# STM32MP25XXAK_I_Os.net
KiCad netlist of a schematic drawn in Altium Designer
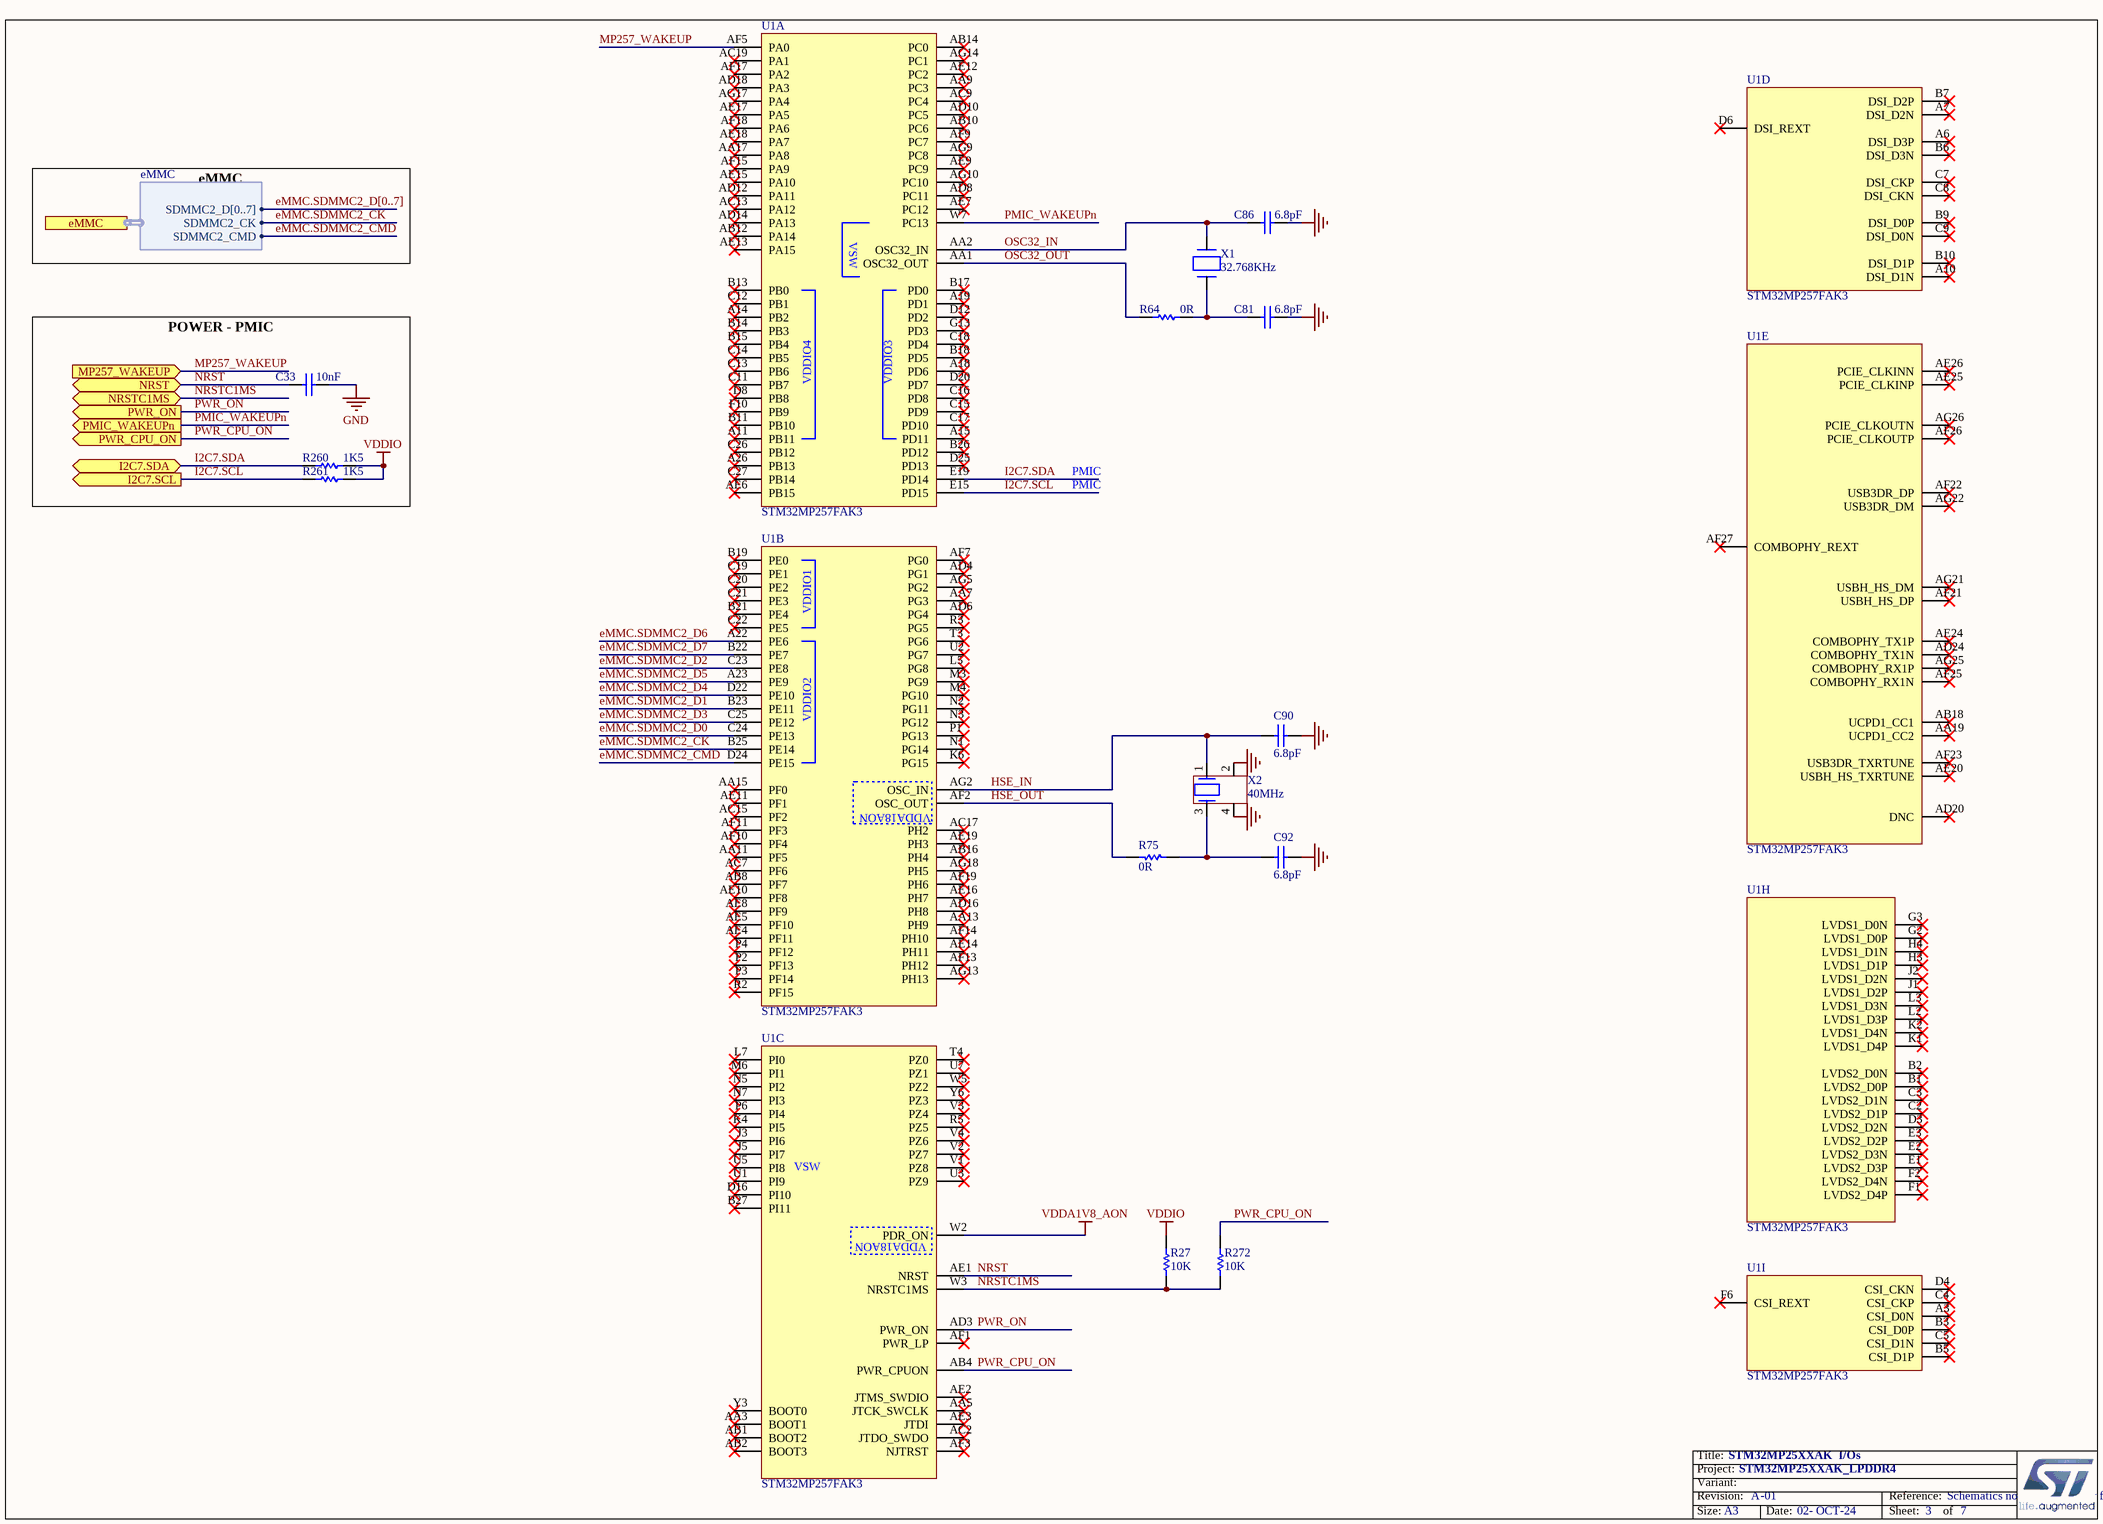
[diagram p0: STM32MP25XXAK I_Os.SchDoc]

(export (version "E")
  (design (tool "Eeschema 10.0.6"))
  (components
    (comp (ref "C33")
      (value "10nF")
      (footprint "C0402")
      (description "Capacitor, MLCC, 10nF, 16V, X7R, 10%, 0402, T=0.5mm")
      (fields
        (field (name "INTERNAL_PART_NUMBER") "MCD-00011")
        (field (name "MANUFACTURER_PART_NUMBER") "CC0402KRX7R7BB103")
        (field (name "PROVIDED_BY") "SUBCO")
      )
      (libsource (lib "MCD_PARTS_database") (part "Capacitor"))
    )
    (comp (ref "C81")
      (value "6.8pF")
      (footprint "C0402")
      (description "Capacitor, MLCC, 6.8pF, 50V, NPO, +-0.25pF, 0402, T=0.5mm")
      (fields
        (field (name "INTERNAL_PART_NUMBER") "MCD-00674")
        (field (name "MANUFACTURER_PART_NUMBER") "CC0402CRNPO9BN6R8")
        (field (name "PROVIDED_BY") "SUBCO")
      )
      (libsource (lib "MCD_PARTS_database") (part "Capacitor"))
    )
    (comp (ref "C86")
      (value "6.8pF")
      (footprint "C0402")
      (description "Capacitor, MLCC, 6.8pF, 50V, NPO, +-0.25pF, 0402, T=0.5mm")
      (fields
        (field (name "INTERNAL_PART_NUMBER") "MCD-00674")
        (field (name "MANUFACTURER_PART_NUMBER") "CC0402CRNPO9BN6R8")
        (field (name "PROVIDED_BY") "SUBCO")
      )
      (libsource (lib "MCD_PARTS_database") (part "Capacitor"))
    )
    (comp (ref "C90")
      (value "6.8pF")
      (footprint "C0402")
      (description "Capacitor, MLCC, 6.8pF, 50V, NPO, +-0.25pF, 0402, T=0.5mm")
      (fields
        (field (name "INTERNAL_PART_NUMBER") "MCD-00674")
        (field (name "MANUFACTURER_PART_NUMBER") "CC0402CRNPO9BN6R8")
        (field (name "PROVIDED_BY") "SUBCO")
      )
      (libsource (lib "MCD_PARTS_database") (part "Capacitor"))
    )
    (comp (ref "C92")
      (value "6.8pF")
      (footprint "C0402")
      (description "Capacitor, MLCC, 6.8pF, 50V, NPO, +-0.25pF, 0402, T=0.5mm")
      (fields
        (field (name "INTERNAL_PART_NUMBER") "MCD-00674")
        (field (name "MANUFACTURER_PART_NUMBER") "CC0402CRNPO9BN6R8")
        (field (name "PROVIDED_BY") "SUBCO")
      )
      (libsource (lib "MCD_PARTS_database") (part "Capacitor"))
    )
    (comp (ref "R27")
      (value "10K")
      (footprint "R0402")
      (description "Resistor,10K,0402,1%,1/16W")
      (fields (field (name "INTERNAL_PART_NUMBER") "MCD-00053") (field (name "BMS_PART_NUMBER") "9131590"))
      (libsource (lib "MCD_PARTS_database") (part "Resistor"))
    )
    (comp (ref "R64")
      (value "0R")
      (footprint "R0402")
      (description "Resistor,0R,0402,5%,1/16W")
      (fields
        (field (name "INTERNAL_PART_NUMBER") "MCD-00052")
        (field (name "MANUFACTURER_PART_NUMBER") "RC0402JR-070RL")
        (field (name "PROVIDED_BY") "SUBCO")
      )
      (libsource (lib "MCD_PARTS_database") (part "Resistor"))
    )
    (comp (ref "R75")
      (value "0R")
      (footprint "R0402")
      (description "Resistor,0R,0402,5%,1/16W")
      (fields
        (field (name "INTERNAL_PART_NUMBER") "MCD-00052")
        (field (name "MANUFACTURER_PART_NUMBER") "RC0402JR-070RL")
        (field (name "PROVIDED_BY") "SUBCO")
      )
      (libsource (lib "MCD_PARTS_database") (part "Resistor"))
    )
    (comp (ref "R260")
      (value "1K5")
      (footprint "R0402")
      (description "Resistor,1K5,0402,1%,1/16W")
      (fields (field (name "INTERNAL_PART_NUMBER") "MCD-00068") (field (name "MANUFACTURER") "YAGEO"))
      (libsource (lib "MCD_PARTS_database") (part "Resistor"))
    )
    (comp (ref "R261")
      (value "1K5")
      (footprint "R0402")
      (description "Resistor,1K5,0402,1%,1/16W")
      (fields (field (name "INTERNAL_PART_NUMBER") "MCD-00068") (field (name "MANUFACTURER") "YAGEO"))
      (libsource (lib "MCD_PARTS_database") (part "Resistor"))
    )
    (comp (ref "R272")
      (value "10K")
      (footprint "R0402")
      (description "Resistor,10K,0402,1%,1/16W")
      (fields (field (name "INTERNAL_PART_NUMBER") "MCD-00053") (field (name "BMS_PART_NUMBER") "9131590"))
      (libsource (lib "MCD_PARTS_database") (part "Resistor"))
    )
    (comp (ref "U1")
      (value "STM32MP257FAK3")
      (footprint "ICC_TFBGA424_14X14_P050_H1P20_CODE-B0A2")
      (description "MPU , 2xCortex-A35@1.5GHz, Cortex-M33@400MHz, TFBGA 14x14, pitch 0.5, 808 KB SRAM, With Crypto")
      (fields
        (field (name "INTERNAL_PART_NUMBER") "MCD-03375")
        (field (name "MANUFACTURER") "STMICROELECTRONICS")
      )
      (libsource (lib "MCD_PARTS_database") (part "STM32MP257FAK3"))
    )
    (comp (ref "X1")
      (value "32.768KHz")
      (footprint "CRY_NX2012SA_2P")
      (description "Crystal, 32.768kHz, 6pF, +/-20ppm, 80K, 2.05x1.2mm")
      (fields (field (name "INTERNAL_PART_NUMBER") "MCD-01479") (field (name "BMS_PART_NUMBER") "9157049"))
      (libsource (lib "MCD_PARTS_database") (part "XTAL_2_PINS"))
    )
    (comp (ref "X2")
      (value "40MHz")
      (footprint "CRY_NX1612SA_4P")
      (description "Crystal, 40MHz, 6pF, +/-20ppm, 80R, 1.6x1.2mm")
      (fields (field (name "INTERNAL_PART_NUMBER") "MCD-02344") (field (name "MANUFACTURER") "NDK"))
      (libsource (lib "MCD_PARTS_database") (part "XTAL_4_PINS"))
    )
  )
  (nets
    (net (code "2") (name "/HSE_IN") (class "Default")
      (node (ref "C90") (pin "2") (pinfunction "2_2") (pintype "passive"))
      (node (ref "U1") (pin "AG2") (pinfunction "OSC_IN_AG2") (pintype "passive"))
      (node (ref "X2") (pin "1") (pinfunction "1_1") (pintype "passive"))
    )
    (net (code "3") (name "/HSE_OUT") (class "Default")
      (node (ref "R75") (pin "2") (pinfunction "2_2") (pintype "passive"))
      (node (ref "U1") (pin "AF2") (pinfunction "OSC_OUT_AF2") (pintype "passive"))
    )
    (net (code "4") (name "/I2C7.SCL") (class "Default")
      (node (ref "R261") (pin "1") (pinfunction "1_1") (pintype "passive"))
      (node (ref "U1") (pin "E15") (pinfunction "PD15_E15") (pintype "passive"))
    )
    (net (code "5") (name "/I2C7.SDA") (class "Default")
      (node (ref "R260") (pin "1") (pinfunction "1_1") (pintype "passive"))
      (node (ref "U1") (pin "E19") (pinfunction "PD14_E19") (pintype "passive"))
    )
    (net (code "6") (name "/MP257_WAKEUP") (class "Default")
      (node (ref "U1") (pin "AF5") (pinfunction "PA0_AF5") (pintype "passive"))
    )
    (net (code "7") (name "/NRST") (class "Default")
      (node (ref "C33") (pin "2") (pinfunction "2_2") (pintype "passive"))
      (node (ref "U1") (pin "AE1") (pinfunction "NRST_AE1") (pintype "passive"))
    )
    (net (code "8") (name "/NRSTC1MS") (class "Default")
      (node (ref "R27") (pin "1") (pinfunction "1_1") (pintype "passive"))
      (node (ref "R272") (pin "1") (pinfunction "1_1") (pintype "passive"))
      (node (ref "U1") (pin "W3") (pinfunction "NRSTC1MS_W3") (pintype "passive"))
    )
    (net (code "9") (name "/OSC32_IN") (class "Default")
      (node (ref "C86") (pin "1") (pinfunction "1_1") (pintype "passive"))
      (node (ref "U1") (pin "AA2") (pinfunction "OSC32_IN_AA2") (pintype "passive"))
      (node (ref "X1") (pin "2") (pinfunction "X2_2") (pintype "passive"))
    )
    (net (code "10") (name "/OSC32_OUT") (class "Default")
      (node (ref "R64") (pin "1") (pinfunction "1_1") (pintype "passive"))
      (node (ref "U1") (pin "AA1") (pinfunction "OSC32_OUT_AA1") (pintype "passive"))
    )
    (net (code "11") (name "/PMIC_WAKEUPn") (class "Default")
      (node (ref "U1") (pin "W7") (pinfunction "PC13_W7") (pintype "passive"))
    )
    (net (code "12") (name "/PWR_CPU_ON") (class "Default")
      (node (ref "R272") (pin "2") (pinfunction "2_2") (pintype "passive"))
      (node (ref "U1") (pin "AB4") (pinfunction "PWR_CPUON_AB4") (pintype "passive"))
    )
    (net (code "13") (name "/PWR_ON") (class "Default")
      (node (ref "U1") (pin "AD3") (pinfunction "PWR_ON_AD3") (pintype "passive"))
    )
    (net (code "14") (name "/eMMC.SDMMC2_CK") (class "Default")
      (node (ref "U1") (pin "B25") (pinfunction "PE14_B25") (pintype "passive"))
    )
    (net (code "15") (name "/eMMC.SDMMC2_CMD") (class "Default")
      (node (ref "U1") (pin "D24") (pinfunction "PE15_D24") (pintype "passive"))
    )
    (net (code "16") (name "/eMMC.SDMMC2_D0") (class "Default")
      (node (ref "U1") (pin "C24") (pinfunction "PE13_C24") (pintype "passive"))
    )
    (net (code "17") (name "/eMMC.SDMMC2_D1") (class "Default")
      (node (ref "U1") (pin "B23") (pinfunction "PE11_B23") (pintype "passive"))
    )
    (net (code "18") (name "/eMMC.SDMMC2_D2") (class "Default")
      (node (ref "U1") (pin "C23") (pinfunction "PE8_C23") (pintype "passive"))
    )
    (net (code "19") (name "/eMMC.SDMMC2_D3") (class "Default")
      (node (ref "U1") (pin "C25") (pinfunction "PE12_C25") (pintype "passive"))
    )
    (net (code "20") (name "/eMMC.SDMMC2_D4") (class "Default")
      (node (ref "U1") (pin "D22") (pinfunction "PE10_D22") (pintype "passive"))
    )
    (net (code "21") (name "/eMMC.SDMMC2_D5") (class "Default")
      (node (ref "U1") (pin "A23") (pinfunction "PE9_A23") (pintype "passive"))
    )
    (net (code "22") (name "/eMMC.SDMMC2_D6") (class "Default")
      (node (ref "U1") (pin "A22") (pinfunction "PE6_A22") (pintype "passive"))
    )
    (net (code "23") (name "/eMMC.SDMMC2_D7") (class "Default")
      (node (ref "U1") (pin "B22") (pinfunction "PE7_B22") (pintype "passive"))
    )
    (net (code "26") (name "GND") (class "Default")
      (node (ref "C33") (pin "1") (pinfunction "1_1") (pintype "passive"))
      (node (ref "C81") (pin "2") (pinfunction "2_2") (pintype "passive"))
      (node (ref "C86") (pin "2") (pinfunction "2_2") (pintype "passive"))
      (node (ref "C90") (pin "1") (pinfunction "1_1") (pintype "passive"))
      (node (ref "C92") (pin "2") (pinfunction "2_2") (pintype "passive"))
      (node (ref "X2") (pin "2") (pinfunction "2_2") (pintype "passive"))
      (node (ref "X2") (pin "4") (pinfunction "4_4") (pintype "passive"))
    )
    (net (code "27") (name "Net-(C92-Pad1)") (class "Default")
      (node (ref "C92") (pin "1") (pinfunction "1_1") (pintype "passive"))
      (node (ref "R75") (pin "1") (pinfunction "1_1") (pintype "passive"))
      (node (ref "X2") (pin "3") (pinfunction "3_3") (pintype "passive"))
    )
    (net (code "28") (name "Net-(X1-X1)") (class "Default")
      (node (ref "C81") (pin "1") (pinfunction "1_1") (pintype "passive"))
      (node (ref "R64") (pin "2") (pinfunction "2_2") (pintype "passive"))
      (node (ref "X1") (pin "1") (pinfunction "X1_1") (pintype "passive"))
    )
    (net (code "29") (name "VDDA1V8_AON") (class "Default")
      (node (ref "U1") (pin "W2") (pinfunction "PDR_ON_W2") (pintype "passive"))
    )
    (net (code "30") (name "VDDIO") (class "Default")
      (node (ref "R260") (pin "2") (pinfunction "2_2") (pintype "passive"))
      (node (ref "R261") (pin "2") (pinfunction "2_2") (pintype "passive"))
      (node (ref "R27") (pin "2") (pinfunction "2_2") (pintype "passive"))
    )
    (net (code "31") (name "unconnected-(U1A-PA1-PadAC19)") (class "Default")
      (node (ref "U1") (pin "AC19") (pinfunction "PA1_AC19") (pintype "passive+no_connect"))
    )
    (net (code "32") (name "unconnected-(U1A-PA2-PadAF17)") (class "Default")
      (node (ref "U1") (pin "AF17") (pinfunction "PA2_AF17") (pintype "passive+no_connect"))
    )
    (net (code "33") (name "unconnected-(U1A-PA3-PadAD18)") (class "Default")
      (node (ref "U1") (pin "AD18") (pinfunction "PA3_AD18") (pintype "passive+no_connect"))
    )
    (net (code "34") (name "unconnected-(U1A-PA4-PadAG17)") (class "Default")
      (node (ref "U1") (pin "AG17") (pinfunction "PA4_AG17") (pintype "passive+no_connect"))
    )
    (net (code "35") (name "unconnected-(U1A-PA5-PadAE17)") (class "Default")
      (node (ref "U1") (pin "AE17") (pinfunction "PA5_AE17") (pintype "passive+no_connect"))
    )
    (net (code "36") (name "unconnected-(U1A-PA6-PadAF18)") (class "Default")
      (node (ref "U1") (pin "AF18") (pinfunction "PA6_AF18") (pintype "passive+no_connect"))
    )
    (net (code "37") (name "unconnected-(U1A-PA7-PadAE18)") (class "Default")
      (node (ref "U1") (pin "AE18") (pinfunction "PA7_AE18") (pintype "passive+no_connect"))
    )
    (net (code "38") (name "unconnected-(U1A-PA8-PadAA17)") (class "Default")
      (node (ref "U1") (pin "AA17") (pinfunction "PA8_AA17") (pintype "passive+no_connect"))
    )
    (net (code "39") (name "unconnected-(U1A-PA9-PadAF15)") (class "Default")
      (node (ref "U1") (pin "AF15") (pinfunction "PA9_AF15") (pintype "passive+no_connect"))
    )
    (net (code "40") (name "unconnected-(U1A-PA10-PadAE15)") (class "Default")
      (node (ref "U1") (pin "AE15") (pinfunction "PA10_AE15") (pintype "passive+no_connect"))
    )
    (net (code "41") (name "unconnected-(U1A-PA11-PadAD12)") (class "Default")
      (node (ref "U1") (pin "AD12") (pinfunction "PA11_AD12") (pintype "passive+no_connect"))
    )
    (net (code "42") (name "unconnected-(U1A-PA12-PadAC13)") (class "Default")
      (node (ref "U1") (pin "AC13") (pinfunction "PA12_AC13") (pintype "passive+no_connect"))
    )
    (net (code "43") (name "unconnected-(U1A-PA13-PadAD14)") (class "Default")
      (node (ref "U1") (pin "AD14") (pinfunction "PA13_AD14") (pintype "passive+no_connect"))
    )
    (net (code "44") (name "unconnected-(U1A-PA14-PadAB12)") (class "Default")
      (node (ref "U1") (pin "AB12") (pinfunction "PA14_AB12") (pintype "passive+no_connect"))
    )
    (net (code "45") (name "unconnected-(U1A-PA15-PadAE13)") (class "Default")
      (node (ref "U1") (pin "AE13") (pinfunction "PA15_AE13") (pintype "passive+no_connect"))
    )
    (net (code "46") (name "unconnected-(U1A-PB0-PadB13)") (class "Default")
      (node (ref "U1") (pin "B13") (pinfunction "PB0_B13") (pintype "passive+no_connect"))
    )
    (net (code "47") (name "unconnected-(U1A-PB1-PadC12)") (class "Default")
      (node (ref "U1") (pin "C12") (pinfunction "PB1_C12") (pintype "passive+no_connect"))
    )
    (net (code "48") (name "unconnected-(U1A-PB2-PadA14)") (class "Default")
      (node (ref "U1") (pin "A14") (pinfunction "PB2_A14") (pintype "passive+no_connect"))
    )
    (net (code "49") (name "unconnected-(U1A-PB3-PadB14)") (class "Default")
      (node (ref "U1") (pin "B14") (pinfunction "PB3_B14") (pintype "passive+no_connect"))
    )
    (net (code "50") (name "unconnected-(U1A-PB4-PadB15)") (class "Default")
      (node (ref "U1") (pin "B15") (pinfunction "PB4_B15") (pintype "passive+no_connect"))
    )
    (net (code "51") (name "unconnected-(U1A-PB5-PadC14)") (class "Default")
      (node (ref "U1") (pin "C14") (pinfunction "PB5_C14") (pintype "passive+no_connect"))
    )
    (net (code "52") (name "unconnected-(U1A-PB6-PadC13)") (class "Default")
      (node (ref "U1") (pin "C13") (pinfunction "PB6_C13") (pintype "passive+no_connect"))
    )
    (net (code "53") (name "unconnected-(U1A-PB7-PadC11)") (class "Default")
      (node (ref "U1") (pin "C11") (pinfunction "PB7_C11") (pintype "passive+no_connect"))
    )
    (net (code "54") (name "unconnected-(U1A-PB8-PadD8)") (class "Default")
      (node (ref "U1") (pin "D8") (pinfunction "PB8_D8") (pintype "passive+no_connect"))
    )
    (net (code "55") (name "unconnected-(U1A-PB9-PadF10)") (class "Default")
      (node (ref "U1") (pin "F10") (pinfunction "PB9_F10") (pintype "passive+no_connect"))
    )
    (net (code "56") (name "unconnected-(U1A-PB10-PadB11)") (class "Default")
      (node (ref "U1") (pin "B11") (pinfunction "PB10_B11") (pintype "passive+no_connect"))
    )
    (net (code "57") (name "unconnected-(U1A-PB11-PadA11)") (class "Default")
      (node (ref "U1") (pin "A11") (pinfunction "PB11_A11") (pintype "passive+no_connect"))
    )
    (net (code "58") (name "unconnected-(U1A-PB12-PadC26)") (class "Default")
      (node (ref "U1") (pin "C26") (pinfunction "PB12_C26") (pintype "passive+no_connect"))
    )
    (net (code "59") (name "unconnected-(U1A-PB13-PadA26)") (class "Default")
      (node (ref "U1") (pin "A26") (pinfunction "PB13_A26") (pintype "passive+no_connect"))
    )
    (net (code "60") (name "unconnected-(U1A-PB14-PadC27)") (class "Default")
      (node (ref "U1") (pin "C27") (pinfunction "PB14_C27") (pintype "passive+no_connect"))
    )
    (net (code "61") (name "unconnected-(U1A-PB15-PadAE6)") (class "Default")
      (node (ref "U1") (pin "AE6") (pinfunction "PB15_AE6") (pintype "passive+no_connect"))
    )
    (net (code "62") (name "unconnected-(U1A-PC0-PadAB14)") (class "Default")
      (node (ref "U1") (pin "AB14") (pinfunction "PC0_AB14") (pintype "passive+no_connect"))
    )
    (net (code "63") (name "unconnected-(U1A-PC1-PadAG14)") (class "Default")
      (node (ref "U1") (pin "AG14") (pinfunction "PC1_AG14") (pintype "passive+no_connect"))
    )
    (net (code "64") (name "unconnected-(U1A-PC2-PadAE12)") (class "Default")
      (node (ref "U1") (pin "AE12") (pinfunction "PC2_AE12") (pintype "passive+no_connect"))
    )
    (net (code "65") (name "unconnected-(U1A-PC3-PadAA9)") (class "Default")
      (node (ref "U1") (pin "AA9") (pinfunction "PC3_AA9") (pintype "passive+no_connect"))
    )
    (net (code "66") (name "unconnected-(U1A-PC4-PadAC9)") (class "Default")
      (node (ref "U1") (pin "AC9") (pinfunction "PC4_AC9") (pintype "passive+no_connect"))
    )
    (net (code "67") (name "unconnected-(U1A-PC5-PadAD10)") (class "Default")
      (node (ref "U1") (pin "AD10") (pinfunction "PC5_AD10") (pintype "passive+no_connect"))
    )
    (net (code "68") (name "unconnected-(U1A-PC6-PadAB10)") (class "Default")
      (node (ref "U1") (pin "AB10") (pinfunction "PC6_AB10") (pintype "passive+no_connect"))
    )
    (net (code "69") (name "unconnected-(U1A-PC7-PadAF9)") (class "Default")
      (node (ref "U1") (pin "AF9") (pinfunction "PC7_AF9") (pintype "passive+no_connect"))
    )
    (net (code "70") (name "unconnected-(U1A-PC8-PadAG9)") (class "Default")
      (node (ref "U1") (pin "AG9") (pinfunction "PC8_AG9") (pintype "passive+no_connect"))
    )
    (net (code "71") (name "unconnected-(U1A-PC9-PadAE9)") (class "Default")
      (node (ref "U1") (pin "AE9") (pinfunction "PC9_AE9") (pintype "passive+no_connect"))
    )
    (net (code "72") (name "unconnected-(U1A-PC10-PadAG10)") (class "Default")
      (node (ref "U1") (pin "AG10") (pinfunction "PC10_AG10") (pintype "passive+no_connect"))
    )
    (net (code "73") (name "unconnected-(U1A-PC11-PadAD8)") (class "Default")
      (node (ref "U1") (pin "AD8") (pinfunction "PC11_AD8") (pintype "passive+no_connect"))
    )
    (net (code "74") (name "unconnected-(U1A-PC12-PadAE7)") (class "Default")
      (node (ref "U1") (pin "AE7") (pinfunction "PC12_AE7") (pintype "passive+no_connect"))
    )
    (net (code "75") (name "unconnected-(U1A-PD0-PadB17)") (class "Default")
      (node (ref "U1") (pin "B17") (pinfunction "PD0_B17") (pintype "passive+no_connect"))
    )
    (net (code "76") (name "unconnected-(U1A-PD1-PadA19)") (class "Default")
      (node (ref "U1") (pin "A19") (pinfunction "PD1_A19") (pintype "passive+no_connect"))
    )
    (net (code "77") (name "unconnected-(U1A-PD2-PadD12)") (class "Default")
      (node (ref "U1") (pin "D12") (pinfunction "PD2_D12") (pintype "passive+no_connect"))
    )
    (net (code "78") (name "unconnected-(U1A-PD3-PadG13)") (class "Default")
      (node (ref "U1") (pin "G13") (pinfunction "PD3_G13") (pintype "passive+no_connect"))
    )
    (net (code "79") (name "unconnected-(U1A-PD4-PadC18)") (class "Default")
      (node (ref "U1") (pin "C18") (pinfunction "PD4_C18") (pintype "passive+no_connect"))
    )
    (net (code "80") (name "unconnected-(U1A-PD5-PadB18)") (class "Default")
      (node (ref "U1") (pin "B18") (pinfunction "PD5_B18") (pintype "passive+no_connect"))
    )
    (net (code "81") (name "unconnected-(U1A-PD6-PadA18)") (class "Default")
      (node (ref "U1") (pin "A18") (pinfunction "PD6_A18") (pintype "passive+no_connect"))
    )
    (net (code "82") (name "unconnected-(U1A-PD7-PadD20)") (class "Default")
      (node (ref "U1") (pin "D20") (pinfunction "PD7_D20") (pintype "passive+no_connect"))
    )
    (net (code "83") (name "unconnected-(U1A-PD8-PadC16)") (class "Default")
      (node (ref "U1") (pin "C16") (pinfunction "PD8_C16") (pintype "passive+no_connect"))
    )
    (net (code "84") (name "unconnected-(U1A-PD9-PadC15)") (class "Default")
      (node (ref "U1") (pin "C15") (pinfunction "PD9_C15") (pintype "passive+no_connect"))
    )
    (net (code "85") (name "unconnected-(U1A-PD10-PadC17)") (class "Default")
      (node (ref "U1") (pin "C17") (pinfunction "PD10_C17") (pintype "passive+no_connect"))
    )
    (net (code "86") (name "unconnected-(U1A-PD11-PadA15)") (class "Default")
      (node (ref "U1") (pin "A15") (pinfunction "PD11_A15") (pintype "passive+no_connect"))
    )
    (net (code "87") (name "unconnected-(U1A-PD12-PadB26)") (class "Default")
      (node (ref "U1") (pin "B26") (pinfunction "PD12_B26") (pintype "passive+no_connect"))
    )
    (net (code "88") (name "unconnected-(U1A-PD13-PadD25)") (class "Default")
      (node (ref "U1") (pin "D25") (pinfunction "PD13_D25") (pintype "passive+no_connect"))
    )
    (net (code "89") (name "unconnected-(U1B-PE0-PadB19)") (class "Default")
      (node (ref "U1") (pin "B19") (pinfunction "PE0_B19") (pintype "passive+no_connect"))
    )
    (net (code "90") (name "unconnected-(U1B-PE1-PadC19)") (class "Default")
      (node (ref "U1") (pin "C19") (pinfunction "PE1_C19") (pintype "passive+no_connect"))
    )
    (net (code "91") (name "unconnected-(U1B-PE2-PadC20)") (class "Default")
      (node (ref "U1") (pin "C20") (pinfunction "PE2_C20") (pintype "passive+no_connect"))
    )
    (net (code "92") (name "unconnected-(U1B-PE3-PadC21)") (class "Default")
      (node (ref "U1") (pin "C21") (pinfunction "PE3_C21") (pintype "passive+no_connect"))
    )
    (net (code "93") (name "unconnected-(U1B-PE4-PadB21)") (class "Default")
      (node (ref "U1") (pin "B21") (pinfunction "PE4_B21") (pintype "passive+no_connect"))
    )
    (net (code "94") (name "unconnected-(U1B-PE5-PadC22)") (class "Default")
      (node (ref "U1") (pin "C22") (pinfunction "PE5_C22") (pintype "passive+no_connect"))
    )
    (net (code "95") (name "unconnected-(U1B-PF0-PadAA15)") (class "Default")
      (node (ref "U1") (pin "AA15") (pinfunction "PF0_AA15") (pintype "passive+no_connect"))
    )
    (net (code "96") (name "unconnected-(U1B-PF1-PadAE11)") (class "Default")
      (node (ref "U1") (pin "AE11") (pinfunction "PF1_AE11") (pintype "passive+no_connect"))
    )
    (net (code "97") (name "unconnected-(U1B-PF2-PadAC15)") (class "Default")
      (node (ref "U1") (pin "AC15") (pinfunction "PF2_AC15") (pintype "passive+no_connect"))
    )
    (net (code "98") (name "unconnected-(U1B-PF3-PadAF11)") (class "Default")
      (node (ref "U1") (pin "AF11") (pinfunction "PF3_AF11") (pintype "passive+no_connect"))
    )
    (net (code "99") (name "unconnected-(U1B-PF4-PadAF10)") (class "Default")
      (node (ref "U1") (pin "AF10") (pinfunction "PF4_AF10") (pintype "passive+no_connect"))
    )
    (net (code "100") (name "unconnected-(U1B-PF5-PadAA11)") (class "Default")
      (node (ref "U1") (pin "AA11") (pinfunction "PF5_AA11") (pintype "passive+no_connect"))
    )
    (net (code "101") (name "unconnected-(U1B-PF6-PadAC7)") (class "Default")
      (node (ref "U1") (pin "AC7") (pinfunction "PF6_AC7") (pintype "passive+no_connect"))
    )
    (net (code "102") (name "unconnected-(U1B-PF7-PadAB8)") (class "Default")
      (node (ref "U1") (pin "AB8") (pinfunction "PF7_AB8") (pintype "passive+no_connect"))
    )
    (net (code "103") (name "unconnected-(U1B-PF8-PadAE10)") (class "Default")
      (node (ref "U1") (pin "AE10") (pinfunction "PF8_AE10") (pintype "passive+no_connect"))
    )
    (net (code "104") (name "unconnected-(U1B-PF9-PadAE8)") (class "Default")
      (node (ref "U1") (pin "AE8") (pinfunction "PF9_AE8") (pintype "passive+no_connect"))
    )
    (net (code "105") (name "unconnected-(U1B-PF10-PadAE5)") (class "Default")
      (node (ref "U1") (pin "AE5") (pinfunction "PF10_AE5") (pintype "passive+no_connect"))
    )
    (net (code "106") (name "unconnected-(U1B-PF11-PadAE4)") (class "Default")
      (node (ref "U1") (pin "AE4") (pinfunction "PF11_AE4") (pintype "passive+no_connect"))
    )
    (net (code "107") (name "unconnected-(U1B-PF12-PadP4)") (class "Default")
      (node (ref "U1") (pin "P4") (pinfunction "PF12_P4") (pintype "passive+no_connect"))
    )
    (net (code "108") (name "unconnected-(U1B-PF13-PadP2)") (class "Default")
      (node (ref "U1") (pin "P2") (pinfunction "PF13_P2") (pintype "passive+no_connect"))
    )
    (net (code "109") (name "unconnected-(U1B-PF14-PadP3)") (class "Default")
      (node (ref "U1") (pin "P3") (pinfunction "PF14_P3") (pintype "passive+no_connect"))
    )
    (net (code "110") (name "unconnected-(U1B-PF15-PadR2)") (class "Default")
      (node (ref "U1") (pin "R2") (pinfunction "PF15_R2") (pintype "passive+no_connect"))
    )
    (net (code "111") (name "unconnected-(U1B-PG0-PadAF7)") (class "Default")
      (node (ref "U1") (pin "AF7") (pinfunction "PG0_AF7") (pintype "passive+no_connect"))
    )
    (net (code "112") (name "unconnected-(U1B-PG1-PadAD4)") (class "Default")
      (node (ref "U1") (pin "AD4") (pinfunction "PG1_AD4") (pintype "passive+no_connect"))
    )
    (net (code "113") (name "unconnected-(U1B-PG2-PadAG5)") (class "Default")
      (node (ref "U1") (pin "AG5") (pinfunction "PG2_AG5") (pintype "passive+no_connect"))
    )
    (net (code "114") (name "unconnected-(U1B-PG3-PadAA7)") (class "Default")
      (node (ref "U1") (pin "AA7") (pinfunction "PG3_AA7") (pintype "passive+no_connect"))
    )
    (net (code "115") (name "unconnected-(U1B-PG4-PadAD6)") (class "Default")
      (node (ref "U1") (pin "AD6") (pinfunction "PG4_AD6") (pintype "passive+no_connect"))
    )
    (net (code "116") (name "unconnected-(U1B-PG5-PadR3)") (class "Default")
      (node (ref "U1") (pin "R3") (pinfunction "PG5_R3") (pintype "passive+no_connect"))
    )
    (net (code "117") (name "unconnected-(U1B-PG6-PadT3)") (class "Default")
      (node (ref "U1") (pin "T3") (pinfunction "PG6_T3") (pintype "passive+no_connect"))
    )
    (net (code "118") (name "unconnected-(U1B-PG7-PadU2)") (class "Default")
      (node (ref "U1") (pin "U2") (pinfunction "PG7_U2") (pintype "passive+no_connect"))
    )
    (net (code "119") (name "unconnected-(U1B-PG8-PadL5)") (class "Default")
      (node (ref "U1") (pin "L5") (pinfunction "PG8_L5") (pintype "passive+no_connect"))
    )
    (net (code "120") (name "unconnected-(U1B-PG9-PadM3)") (class "Default")
      (node (ref "U1") (pin "M3") (pinfunction "PG9_M3") (pintype "passive+no_connect"))
    )
    (net (code "121") (name "unconnected-(U1B-PG10-PadM4)") (class "Default")
      (node (ref "U1") (pin "M4") (pinfunction "PG10_M4") (pintype "passive+no_connect"))
    )
    (net (code "122") (name "unconnected-(U1B-PG11-PadN2)") (class "Default")
      (node (ref "U1") (pin "N2") (pinfunction "PG11_N2") (pintype "passive+no_connect"))
    )
    (net (code "123") (name "unconnected-(U1B-PG12-PadN3)") (class "Default")
      (node (ref "U1") (pin "N3") (pinfunction "PG12_N3") (pintype "passive+no_connect"))
    )
    (net (code "124") (name "unconnected-(U1B-PG13-PadP1)") (class "Default")
      (node (ref "U1") (pin "P1") (pinfunction "PG13_P1") (pintype "passive+no_connect"))
    )
    (net (code "125") (name "unconnected-(U1B-PG14-PadN1)") (class "Default")
      (node (ref "U1") (pin "N1") (pinfunction "PG14_N1") (pintype "passive+no_connect"))
    )
    (net (code "126") (name "unconnected-(U1B-PG15-PadK6)") (class "Default")
      (node (ref "U1") (pin "K6") (pinfunction "PG15_K6") (pintype "passive+no_connect"))
    )
    (net (code "127") (name "unconnected-(U1B-PH2-PadAC17)") (class "Default")
      (node (ref "U1") (pin "AC17") (pinfunction "PH2_AC17") (pintype "passive+no_connect"))
    )
    (net (code "128") (name "unconnected-(U1B-PH3-PadAE19)") (class "Default")
      (node (ref "U1") (pin "AE19") (pinfunction "PH3_AE19") (pintype "passive+no_connect"))
    )
    (net (code "129") (name "unconnected-(U1B-PH4-PadAB16)") (class "Default")
      (node (ref "U1") (pin "AB16") (pinfunction "PH4_AB16") (pintype "passive+no_connect"))
    )
    (net (code "130") (name "unconnected-(U1B-PH5-PadAG18)") (class "Default")
      (node (ref "U1") (pin "AG18") (pinfunction "PH5_AG18") (pintype "passive+no_connect"))
    )
    (net (code "131") (name "unconnected-(U1B-PH6-PadAF19)") (class "Default")
      (node (ref "U1") (pin "AF19") (pinfunction "PH6_AF19") (pintype "passive+no_connect"))
    )
    (net (code "132") (name "unconnected-(U1B-PH7-PadAE16)") (class "Default")
      (node (ref "U1") (pin "AE16") (pinfunction "PH7_AE16") (pintype "passive+no_connect"))
    )
    (net (code "133") (name "unconnected-(U1B-PH8-PadAD16)") (class "Default")
      (node (ref "U1") (pin "AD16") (pinfunction "PH8_AD16") (pintype "passive+no_connect"))
    )
    (net (code "134") (name "unconnected-(U1B-PH9-PadAA13)") (class "Default")
      (node (ref "U1") (pin "AA13") (pinfunction "PH9_AA13") (pintype "passive+no_connect"))
    )
    (net (code "135") (name "unconnected-(U1B-PH10-PadAF14)") (class "Default")
      (node (ref "U1") (pin "AF14") (pinfunction "PH10_AF14") (pintype "passive+no_connect"))
    )
    (net (code "136") (name "unconnected-(U1B-PH11-PadAE14)") (class "Default")
      (node (ref "U1") (pin "AE14") (pinfunction "PH11_AE14") (pintype "passive+no_connect"))
    )
    (net (code "137") (name "unconnected-(U1B-PH12-PadAF13)") (class "Default")
      (node (ref "U1") (pin "AF13") (pinfunction "PH12_AF13") (pintype "passive+no_connect"))
    )
    (net (code "138") (name "unconnected-(U1B-PH13-PadAG13)") (class "Default")
      (node (ref "U1") (pin "AG13") (pinfunction "PH13_AG13") (pintype "passive+no_connect"))
    )
    (net (code "139") (name "unconnected-(U1C-BOOT0-PadY3)") (class "Default")
      (node (ref "U1") (pin "Y3") (pinfunction "BOOT0_Y3") (pintype "passive+no_connect"))
    )
    (net (code "140") (name "unconnected-(U1C-BOOT1-PadAA3)") (class "Default")
      (node (ref "U1") (pin "AA3") (pinfunction "BOOT1_AA3") (pintype "passive+no_connect"))
    )
    (net (code "141") (name "unconnected-(U1C-BOOT2-PadAB1)") (class "Default")
      (node (ref "U1") (pin "AB1") (pinfunction "BOOT2_AB1") (pintype "passive+no_connect"))
    )
    (net (code "142") (name "unconnected-(U1C-BOOT3-PadAB2)") (class "Default")
      (node (ref "U1") (pin "AB2") (pinfunction "BOOT3_AB2") (pintype "passive+no_connect"))
    )
    (net (code "143") (name "unconnected-(U1C-JTCK_SWCLK-PadAA5)") (class "Default")
      (node (ref "U1") (pin "AA5") (pinfunction "JTCK_SWCLK_AA5") (pintype "passive+no_connect"))
    )
    (net (code "144") (name "unconnected-(U1C-JTDI-PadAE3)") (class "Default")
      (node (ref "U1") (pin "AE3") (pinfunction "JTDI_AE3") (pintype "passive+no_connect"))
    )
    (net (code "145") (name "unconnected-(U1C-JTDO_SWDO-PadAC2)") (class "Default")
      (node (ref "U1") (pin "AC2") (pinfunction "JTDO_SWDO_AC2") (pintype "passive+no_connect"))
    )
    (net (code "146") (name "unconnected-(U1C-JTMS_SWDIO-PadAE2)") (class "Default")
      (node (ref "U1") (pin "AE2") (pinfunction "JTMS_SWDIO_AE2") (pintype "passive+no_connect"))
    )
    (net (code "147") (name "unconnected-(U1C-NJTRST-PadAF3)") (class "Default")
      (node (ref "U1") (pin "AF3") (pinfunction "NJTRST_AF3") (pintype "passive+no_connect"))
    )
    (net (code "148") (name "unconnected-(U1C-PI0-PadL7)") (class "Default")
      (node (ref "U1") (pin "L7") (pinfunction "PI0_L7") (pintype "passive+no_connect"))
    )
    (net (code "149") (name "unconnected-(U1C-PI1-PadM6)") (class "Default")
      (node (ref "U1") (pin "M6") (pinfunction "PI1_M6") (pintype "passive+no_connect"))
    )
    (net (code "150") (name "unconnected-(U1C-PI2-PadN5)") (class "Default")
      (node (ref "U1") (pin "N5") (pinfunction "PI2_N5") (pintype "passive+no_connect"))
    )
    (net (code "151") (name "unconnected-(U1C-PI3-PadN7)") (class "Default")
      (node (ref "U1") (pin "N7") (pinfunction "PI3_N7") (pintype "passive+no_connect"))
    )
    (net (code "152") (name "unconnected-(U1C-PI4-PadP6)") (class "Default")
      (node (ref "U1") (pin "P6") (pinfunction "PI4_P6") (pintype "passive+no_connect"))
    )
    (net (code "153") (name "unconnected-(U1C-PI5-PadK4)") (class "Default")
      (node (ref "U1") (pin "K4") (pinfunction "PI5_K4") (pintype "passive+no_connect"))
    )
    (net (code "154") (name "unconnected-(U1C-PI6-PadJ3)") (class "Default")
      (node (ref "U1") (pin "J3") (pinfunction "PI6_J3") (pintype "passive+no_connect"))
    )
    (net (code "155") (name "unconnected-(U1C-PI7-PadJ5)") (class "Default")
      (node (ref "U1") (pin "J5") (pinfunction "PI7_J5") (pintype "passive+no_connect"))
    )
    (net (code "156") (name "unconnected-(U1C-PI8-PadU5)") (class "Default")
      (node (ref "U1") (pin "U5") (pinfunction "PI8_U5") (pintype "passive+no_connect"))
    )
    (net (code "157") (name "unconnected-(U1C-PI9-PadU1)") (class "Default")
      (node (ref "U1") (pin "U1") (pinfunction "PI9_U1") (pintype "passive+no_connect"))
    )
    (net (code "158") (name "unconnected-(U1C-PI10-PadD16)") (class "Default")
      (node (ref "U1") (pin "D16") (pinfunction "PI10_D16") (pintype "passive+no_connect"))
    )
    (net (code "159") (name "unconnected-(U1C-PI11-PadB27)") (class "Default")
      (node (ref "U1") (pin "B27") (pinfunction "PI11_B27") (pintype "passive+no_connect"))
    )
    (net (code "160") (name "unconnected-(U1C-PWR_LP-PadAF1)") (class "Default")
      (node (ref "U1") (pin "AF1") (pinfunction "PWR_LP_AF1") (pintype "passive+no_connect"))
    )
    (net (code "161") (name "unconnected-(U1C-PZ0-PadT4)") (class "Default")
      (node (ref "U1") (pin "T4") (pinfunction "PZ0_T4") (pintype "passive+no_connect"))
    )
    (net (code "162") (name "unconnected-(U1C-PZ1-PadU7)") (class "Default")
      (node (ref "U1") (pin "U7") (pinfunction "PZ1_U7") (pintype "passive+no_connect"))
    )
    (net (code "163") (name "unconnected-(U1C-PZ2-PadW5)") (class "Default")
      (node (ref "U1") (pin "W5") (pinfunction "PZ2_W5") (pintype "passive+no_connect"))
    )
    (net (code "164") (name "unconnected-(U1C-PZ3-PadY6)") (class "Default")
      (node (ref "U1") (pin "Y6") (pinfunction "PZ3_Y6") (pintype "passive+no_connect"))
    )
    (net (code "165") (name "unconnected-(U1C-PZ4-PadV3)") (class "Default")
      (node (ref "U1") (pin "V3") (pinfunction "PZ4_V3") (pintype "passive+no_connect"))
    )
    (net (code "166") (name "unconnected-(U1C-PZ5-PadR5)") (class "Default")
      (node (ref "U1") (pin "R5") (pinfunction "PZ5_R5") (pintype "passive+no_connect"))
    )
    (net (code "167") (name "unconnected-(U1C-PZ6-PadV4)") (class "Default")
      (node (ref "U1") (pin "V4") (pinfunction "PZ6_V4") (pintype "passive+no_connect"))
    )
    (net (code "168") (name "unconnected-(U1C-PZ7-PadV2)") (class "Default")
      (node (ref "U1") (pin "V2") (pinfunction "PZ7_V2") (pintype "passive+no_connect"))
    )
    (net (code "169") (name "unconnected-(U1C-PZ8-PadV1)") (class "Default")
      (node (ref "U1") (pin "V1") (pinfunction "PZ8_V1") (pintype "passive+no_connect"))
    )
    (net (code "170") (name "unconnected-(U1C-PZ9-PadU3)") (class "Default")
      (node (ref "U1") (pin "U3") (pinfunction "PZ9_U3") (pintype "passive+no_connect"))
    )
    (net (code "171") (name "unconnected-(U1D-DSI_CKN-PadC8)") (class "Default")
      (node (ref "U1") (pin "C8") (pinfunction "DSI_CKN_C8") (pintype "passive+no_connect"))
    )
    (net (code "172") (name "unconnected-(U1D-DSI_CKP-PadC7)") (class "Default")
      (node (ref "U1") (pin "C7") (pinfunction "DSI_CKP_C7") (pintype "passive+no_connect"))
    )
    (net (code "173") (name "unconnected-(U1D-DSI_D0N-PadC9)") (class "Default")
      (node (ref "U1") (pin "C9") (pinfunction "DSI_D0N_C9") (pintype "passive+no_connect"))
    )
    (net (code "174") (name "unconnected-(U1D-DSI_D0P-PadB9)") (class "Default")
      (node (ref "U1") (pin "B9") (pinfunction "DSI_D0P_B9") (pintype "passive+no_connect"))
    )
    (net (code "175") (name "unconnected-(U1D-DSI_D1N-PadA10)") (class "Default")
      (node (ref "U1") (pin "A10") (pinfunction "DSI_D1N_A10") (pintype "passive+no_connect"))
    )
    (net (code "176") (name "unconnected-(U1D-DSI_D1P-PadB10)") (class "Default")
      (node (ref "U1") (pin "B10") (pinfunction "DSI_D1P_B10") (pintype "passive+no_connect"))
    )
    (net (code "177") (name "unconnected-(U1D-DSI_D2N-PadA7)") (class "Default")
      (node (ref "U1") (pin "A7") (pinfunction "DSI_D2N_A7") (pintype "passive+no_connect"))
    )
    (net (code "178") (name "unconnected-(U1D-DSI_D2P-PadB7)") (class "Default")
      (node (ref "U1") (pin "B7") (pinfunction "DSI_D2P_B7") (pintype "passive+no_connect"))
    )
    (net (code "179") (name "unconnected-(U1D-DSI_D3N-PadB6)") (class "Default")
      (node (ref "U1") (pin "B6") (pinfunction "DSI_D3N_B6") (pintype "passive+no_connect"))
    )
    (net (code "180") (name "unconnected-(U1D-DSI_D3P-PadA6)") (class "Default")
      (node (ref "U1") (pin "A6") (pinfunction "DSI_D3P_A6") (pintype "passive+no_connect"))
    )
    (net (code "181") (name "unconnected-(U1D-DSI_REXT-PadD6)") (class "Default")
      (node (ref "U1") (pin "D6") (pinfunction "DSI_REXT_D6") (pintype "passive+no_connect"))
    )
    (net (code "182") (name "unconnected-(U1E-COMBOPHY_REXT-PadAF27)") (class "Default")
      (node (ref "U1") (pin "AF27") (pinfunction "COMBOPHY_REXT_AF27") (pintype "passive+no_connect"))
    )
    (net (code "183") (name "unconnected-(U1E-COMBOPHY_RX1N-PadAF25)") (class "Default")
      (node (ref "U1") (pin "AF25") (pinfunction "COMBOPHY_RX1N_AF25") (pintype "passive+no_connect"))
    )
    (net (code "184") (name "unconnected-(U1E-COMBOPHY_RX1P-PadAG25)") (class "Default")
      (node (ref "U1") (pin "AG25") (pinfunction "COMBOPHY_RX1P_AG25") (pintype "passive+no_connect"))
    )
    (net (code "185") (name "unconnected-(U1E-COMBOPHY_TX1N-PadAD24)") (class "Default")
      (node (ref "U1") (pin "AD24") (pinfunction "COMBOPHY_TX1N_AD24") (pintype "passive+no_connect"))
    )
    (net (code "186") (name "unconnected-(U1E-COMBOPHY_TX1P-PadAE24)") (class "Default")
      (node (ref "U1") (pin "AE24") (pinfunction "COMBOPHY_TX1P_AE24") (pintype "passive+no_connect"))
    )
    (net (code "187") (name "unconnected-(U1E-DNC-PadAD20)") (class "Default")
      (node (ref "U1") (pin "AD20") (pinfunction "DNC_AD20") (pintype "passive+no_connect"))
    )
    (net (code "188") (name "unconnected-(U1E-PCIE_CLKINN-PadAE26)") (class "Default")
      (node (ref "U1") (pin "AE26") (pinfunction "PCIE_CLKINN_AE26") (pintype "passive+no_connect"))
    )
    (net (code "189") (name "unconnected-(U1E-PCIE_CLKINP-PadAE25)") (class "Default")
      (node (ref "U1") (pin "AE25") (pinfunction "PCIE_CLKINP_AE25") (pintype "passive+no_connect"))
    )
    (net (code "190") (name "unconnected-(U1E-PCIE_CLKOUTN-PadAG26)") (class "Default")
      (node (ref "U1") (pin "AG26") (pinfunction "PCIE_CLKOUTN_AG26") (pintype "passive+no_connect"))
    )
    (net (code "191") (name "unconnected-(U1E-PCIE_CLKOUTP-PadAF26)") (class "Default")
      (node (ref "U1") (pin "AF26") (pinfunction "PCIE_CLKOUTP_AF26") (pintype "passive+no_connect"))
    )
    (net (code "192") (name "unconnected-(U1E-UCPD1_CC1-PadAB18)") (class "Default")
      (node (ref "U1") (pin "AB18") (pinfunction "UCPD1_CC1_AB18") (pintype "passive+no_connect"))
    )
    (net (code "193") (name "unconnected-(U1E-UCPD1_CC2-PadAA19)") (class "Default")
      (node (ref "U1") (pin "AA19") (pinfunction "UCPD1_CC2_AA19") (pintype "passive+no_connect"))
    )
    (net (code "194") (name "unconnected-(U1E-USB3DR_DM-PadAG22)") (class "Default")
      (node (ref "U1") (pin "AG22") (pinfunction "USB3DR_DM_AG22") (pintype "passive+no_connect"))
    )
    (net (code "195") (name "unconnected-(U1E-USB3DR_DP-PadAF22)") (class "Default")
      (node (ref "U1") (pin "AF22") (pinfunction "USB3DR_DP_AF22") (pintype "passive+no_connect"))
    )
    (net (code "196") (name "unconnected-(U1E-USB3DR_TXRTUNE-PadAF23)") (class "Default")
      (node (ref "U1") (pin "AF23") (pinfunction "USB3DR_TXRTUNE_AF23") (pintype "passive+no_connect"))
    )
    (net (code "197") (name "unconnected-(U1E-USBH_HS_DM-PadAG21)") (class "Default")
      (node (ref "U1") (pin "AG21") (pinfunction "USBH_HS_DM_AG21") (pintype "passive+no_connect"))
    )
    (net (code "198") (name "unconnected-(U1E-USBH_HS_DP-PadAF21)") (class "Default")
      (node (ref "U1") (pin "AF21") (pinfunction "USBH_HS_DP_AF21") (pintype "passive+no_connect"))
    )
    (net (code "199") (name "unconnected-(U1E-USBH_HS_TXRTUNE-PadAE20)") (class "Default")
      (node (ref "U1") (pin "AE20") (pinfunction "USBH_HS_TXRTUNE_AE20") (pintype "passive+no_connect"))
    )
    (net (code "200") (name "unconnected-(U1H-LVDS1_D0N-PadG3)") (class "Default")
      (node (ref "U1") (pin "G3") (pinfunction "LVDS1_D0N_G3") (pintype "passive+no_connect"))
    )
    (net (code "201") (name "unconnected-(U1H-LVDS1_D0P-PadG2)") (class "Default")
      (node (ref "U1") (pin "G2") (pinfunction "LVDS1_D0P_G2") (pintype "passive+no_connect"))
    )
    (net (code "202") (name "unconnected-(U1H-LVDS1_D1N-PadH4)") (class "Default")
      (node (ref "U1") (pin "H4") (pinfunction "LVDS1_D1N_H4") (pintype "passive+no_connect"))
    )
    (net (code "203") (name "unconnected-(U1H-LVDS1_D1P-PadH3)") (class "Default")
      (node (ref "U1") (pin "H3") (pinfunction "LVDS1_D1P_H3") (pintype "passive+no_connect"))
    )
    (net (code "204") (name "unconnected-(U1H-LVDS1_D2N-PadJ2)") (class "Default")
      (node (ref "U1") (pin "J2") (pinfunction "LVDS1_D2N_J2") (pintype "passive+no_connect"))
    )
    (net (code "205") (name "unconnected-(U1H-LVDS1_D2P-PadJ1)") (class "Default")
      (node (ref "U1") (pin "J1") (pinfunction "LVDS1_D2P_J1") (pintype "passive+no_connect"))
    )
    (net (code "206") (name "unconnected-(U1H-LVDS1_D3N-PadL3)") (class "Default")
      (node (ref "U1") (pin "L3") (pinfunction "LVDS1_D3N_L3") (pintype "passive+no_connect"))
    )
    (net (code "207") (name "unconnected-(U1H-LVDS1_D3P-PadL2)") (class "Default")
      (node (ref "U1") (pin "L2") (pinfunction "LVDS1_D3P_L2") (pintype "passive+no_connect"))
    )
    (net (code "208") (name "unconnected-(U1H-LVDS1_D4N-PadK2)") (class "Default")
      (node (ref "U1") (pin "K2") (pinfunction "LVDS1_D4N_K2") (pintype "passive+no_connect"))
    )
    (net (code "209") (name "unconnected-(U1H-LVDS1_D4P-PadK1)") (class "Default")
      (node (ref "U1") (pin "K1") (pinfunction "LVDS1_D4P_K1") (pintype "passive+no_connect"))
    )
    (net (code "210") (name "unconnected-(U1H-LVDS2_D0N-PadB2)") (class "Default")
      (node (ref "U1") (pin "B2") (pinfunction "LVDS2_D0N_B2") (pintype "passive+no_connect"))
    )
    (net (code "211") (name "unconnected-(U1H-LVDS2_D0P-PadB1)") (class "Default")
      (node (ref "U1") (pin "B1") (pinfunction "LVDS2_D0P_B1") (pintype "passive+no_connect"))
    )
    (net (code "212") (name "unconnected-(U1H-LVDS2_D1N-PadC3)") (class "Default")
      (node (ref "U1") (pin "C3") (pinfunction "LVDS2_D1N_C3") (pintype "passive+no_connect"))
    )
    (net (code "213") (name "unconnected-(U1H-LVDS2_D1P-PadC2)") (class "Default")
      (node (ref "U1") (pin "C2") (pinfunction "LVDS2_D1P_C2") (pintype "passive+no_connect"))
    )
    (net (code "214") (name "unconnected-(U1H-LVDS2_D2N-PadD3)") (class "Default")
      (node (ref "U1") (pin "D3") (pinfunction "LVDS2_D2N_D3") (pintype "passive+no_connect"))
    )
    (net (code "215") (name "unconnected-(U1H-LVDS2_D2P-PadE3)") (class "Default")
      (node (ref "U1") (pin "E3") (pinfunction "LVDS2_D2P_E3") (pintype "passive+no_connect"))
    )
    (net (code "216") (name "unconnected-(U1H-LVDS2_D3N-PadE2)") (class "Default")
      (node (ref "U1") (pin "E2") (pinfunction "LVDS2_D3N_E2") (pintype "passive+no_connect"))
    )
    (net (code "217") (name "unconnected-(U1H-LVDS2_D3P-PadE1)") (class "Default")
      (node (ref "U1") (pin "E1") (pinfunction "LVDS2_D3P_E1") (pintype "passive+no_connect"))
    )
    (net (code "218") (name "unconnected-(U1H-LVDS2_D4N-PadF2)") (class "Default")
      (node (ref "U1") (pin "F2") (pinfunction "LVDS2_D4N_F2") (pintype "passive+no_connect"))
    )
    (net (code "219") (name "unconnected-(U1H-LVDS2_D4P-PadF1)") (class "Default")
      (node (ref "U1") (pin "F1") (pinfunction "LVDS2_D4P_F1") (pintype "passive+no_connect"))
    )
    (net (code "220") (name "unconnected-(U1I-CSI_CKN-PadD4)") (class "Default")
      (node (ref "U1") (pin "D4") (pinfunction "CSI_CKN_D4") (pintype "passive+no_connect"))
    )
    (net (code "221") (name "unconnected-(U1I-CSI_CKP-PadC4)") (class "Default")
      (node (ref "U1") (pin "C4") (pinfunction "CSI_CKP_C4") (pintype "passive+no_connect"))
    )
    (net (code "222") (name "unconnected-(U1I-CSI_D0N-PadA3)") (class "Default")
      (node (ref "U1") (pin "A3") (pinfunction "CSI_D0N_A3") (pintype "passive+no_connect"))
    )
    (net (code "223") (name "unconnected-(U1I-CSI_D0P-PadB3)") (class "Default")
      (node (ref "U1") (pin "B3") (pinfunction "CSI_D0P_B3") (pintype "passive+no_connect"))
    )
    (net (code "224") (name "unconnected-(U1I-CSI_D1N-PadC5)") (class "Default")
      (node (ref "U1") (pin "C5") (pinfunction "CSI_D1N_C5") (pintype "passive+no_connect"))
    )
    (net (code "225") (name "unconnected-(U1I-CSI_D1P-PadB5)") (class "Default")
      (node (ref "U1") (pin "B5") (pinfunction "CSI_D1P_B5") (pintype "passive+no_connect"))
    )
    (net (code "226") (name "unconnected-(U1I-CSI_REXT-PadF6)") (class "Default")
      (node (ref "U1") (pin "F6") (pinfunction "CSI_REXT_F6") (pintype "passive+no_connect"))
    )
  )
)
